# MF-CI_4_1-SDW_-_EXTERNAL.net
KiCad netlist of a schematic drawn in Altium Designer
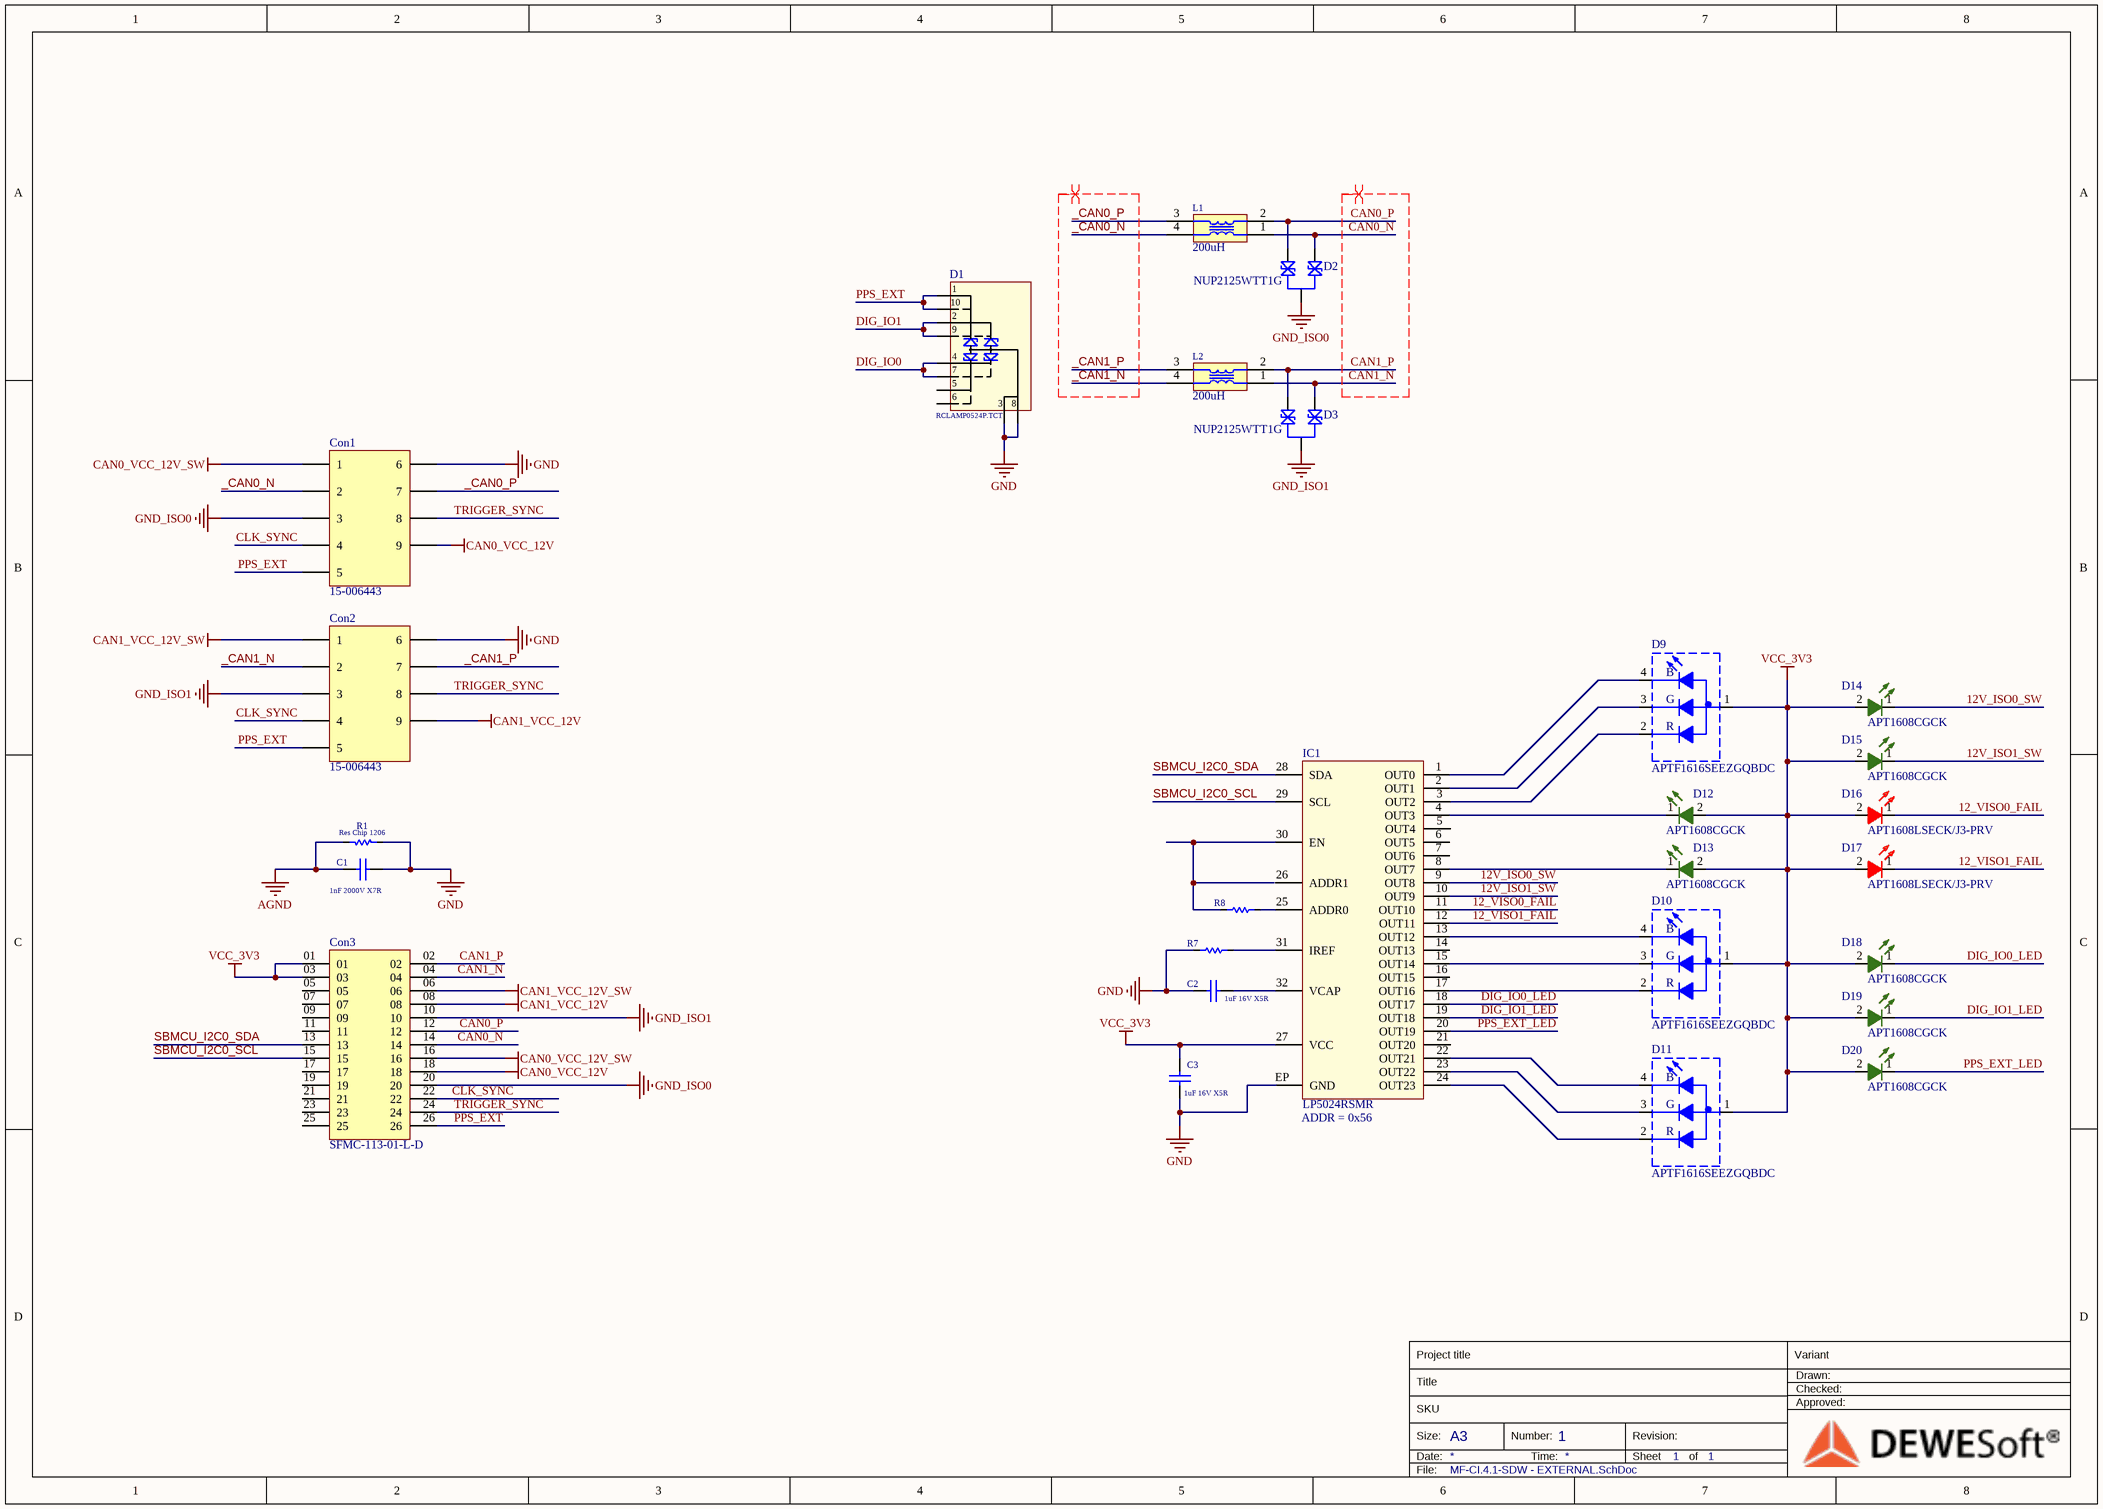
[diagram p0: MF-CI.4.1-SDW - EXTERNAL.SchDoc]

(export (version "E")
  (design (tool "Eeschema 10.0.6"))
  (components
    (comp (ref "C1")
      (value "1nF 2000V X7R")
      (footprint "1206")
      (description "Cap Chip 1nF 2000V X7R 1206")
      (libsource (lib "BBDAQ") (part "Cap"))
    )
    (comp (ref "C2")
      (value "1uF 16V X5R")
      (footprint "0402")
      (description "Capacitor, 1u, 16V, 10%, X5R, 0402")
      (libsource (lib "BBDAQ") (part "CC0402KRX5R7BB105"))
    )
    (comp (ref "C3")
      (value "1uF 16V X5R")
      (footprint "0402")
      (description "Capacitor, 1u, 16V, 10%, X5R, 0402")
      (libsource (lib "BBDAQ") (part "CC0402KRX5R7BB105"))
    )
    (comp (ref "Con1")
      (value "15-006443")
      (footprint "DSUB-9 Male D, 2.74")
      (description "Conn, D-Sub, Male, 9, 2mm, Str, -40/+105")
      (libsource (lib "BBDAQ") (part "15-006443"))
    )
    (comp (ref "Con2")
      (value "15-006443")
      (footprint "DSUB-9 Male D, 2.74")
      (description "Conn, D-Sub, Male, 9, 2mm, Str, -40/+105")
      (libsource (lib "BBDAQ") (part "15-006443"))
    )
    (comp (ref "Con3")
      (value "SFMC-113-01-L-D")
      (footprint "SAMTEC_SFMC-113-01-L-D")
      (description "Conn, Receptacle, Female, 13x2, 1.27mm, Vertical, -55/+125")
      (libsource (lib "BBDAQ") (part "SFMC-113-01-L-D"))
    )
    (comp (ref "D1")
      (value "RCLAMP0524P.TCT")
      (footprint "SLP2510P8")
      (description "Diode array TVS, RCLAMP0524P.TCT")
      (libsource (lib "BBDAQ") (part "CMP-SEM-000069"))
    )
    (comp (ref "D2")
      (value "NUP2125WTT1G")
      (footprint "SOT323-3L(SC-70)")
      (description "Diode dual TVS, SOT323, bidrectional, CAN-FD")
      (libsource (lib "BBDAQ") (part "dual_TVS_diode"))
    )
    (comp (ref "D3")
      (value "NUP2125WTT1G")
      (footprint "SOT323-3L(SC-70)")
      (description "Diode dual TVS, SOT323, bidrectional, CAN-FD")
      (libsource (lib "BBDAQ") (part "dual_TVS_diode"))
    )
    (comp (ref "D9")
      (value "APTF1616SEEZGQBDC")
      (footprint "KINGBRIGHT_APTF1616SEEZGQBDC")
      (description "Diode, LED, Red/Green/Blue, 5V, 20mA, -40/+85")
      (libsource (lib "BBDAQ") (part "APTF1616SEEZGQBDC"))
    )
    (comp (ref "D10")
      (value "APTF1616SEEZGQBDC")
      (footprint "KINGBRIGHT_APTF1616SEEZGQBDC")
      (description "Diode, LED, Red/Green/Blue, 5V, 20mA, -40/+85")
      (libsource (lib "BBDAQ") (part "APTF1616SEEZGQBDC"))
    )
    (comp (ref "D11")
      (value "APTF1616SEEZGQBDC")
      (footprint "KINGBRIGHT_APTF1616SEEZGQBDC")
      (description "Diode, LED, Red/Green/Blue, 5V, 20mA, -40/+85")
      (libsource (lib "BBDAQ") (part "APTF1616SEEZGQBDC"))
    )
    (comp (ref "D12")
      (value "APT1608CGCK")
      (footprint "APT1608CGCK")
      (description "Diode, LED, Green, 5V, 20mA, Vertical, -40/+85, 0603")
      (libsource (lib "BBDAQ") (part "APT1608CGCK"))
    )
    (comp (ref "D13")
      (value "APT1608CGCK")
      (footprint "APT1608CGCK")
      (description "Diode, LED, Green, 5V, 20mA, Vertical, -40/+85, 0603")
      (libsource (lib "BBDAQ") (part "APT1608CGCK"))
    )
    (comp (ref "D14")
      (value "APT1608CGCK")
      (footprint "APT1608CGCK")
      (description "Diode, LED, Green, 5V, 20mA, Vertical, -40/+85, 0603")
      (libsource (lib "BBDAQ") (part "APT1608CGCK"))
    )
    (comp (ref "D15")
      (value "APT1608CGCK")
      (footprint "APT1608CGCK")
      (description "Diode, LED, Green, 5V, 20mA, Vertical, -40/+85, 0603")
      (libsource (lib "BBDAQ") (part "APT1608CGCK"))
    )
    (comp (ref "D16")
      (value "APT1608LSECK/J3-PRV")
      (footprint "Kingbright_APT1608LSECK/J3-PRV")
      (description "Diode, LED, Red, 5V, 20mA, -40/+85")
      (libsource (lib "BBDAQ") (part "APT1608LSECK/J3-PRV"))
    )
    (comp (ref "D17")
      (value "APT1608LSECK/J3-PRV")
      (footprint "Kingbright_APT1608LSECK/J3-PRV")
      (description "Diode, LED, Red, 5V, 20mA, -40/+85")
      (libsource (lib "BBDAQ") (part "APT1608LSECK/J3-PRV"))
    )
    (comp (ref "D18")
      (value "APT1608CGCK")
      (footprint "APT1608CGCK")
      (description "Diode, LED, Green, 5V, 20mA, Vertical, -40/+85, 0603")
      (libsource (lib "BBDAQ") (part "APT1608CGCK"))
    )
    (comp (ref "D19")
      (value "APT1608CGCK")
      (footprint "APT1608CGCK")
      (description "Diode, LED, Green, 5V, 20mA, Vertical, -40/+85, 0603")
      (libsource (lib "BBDAQ") (part "APT1608CGCK"))
    )
    (comp (ref "D20")
      (value "APT1608CGCK")
      (footprint "APT1608CGCK")
      (description "Diode, LED, Green, 5V, 20mA, Vertical, -40/+85, 0603")
      (libsource (lib "BBDAQ") (part "APT1608CGCK"))
    )
    (comp (ref "IC1")
      (value "LP5024RSMR")
      (footprint "QFN-32[8x8]_0,25/0,50_5x5x1_HD[2,10x2,10]")
      (description "IC, LED Driver, 24 LEDs, 2.7-5.5V, 35mA, -40/+85, VFQFN-32")
      (fields (field (name "MANUFACTURER") "TI"))
      (libsource (lib "BBDAQ") (part "LP5024RSMR"))
    )
    (comp (ref "L1")
      (value "200uH")
      (footprint "ACT1210L")
      (description "ACT1210L-201-2P-TL00 -  Filter Common Mode ACT1210L Series 200uH 70mA 2.5mm x 3.9mm x 2.5mm")
      (libsource (lib "BBDAQ") (part "CM_Choke"))
    )
    (comp (ref "L2")
      (value "200uH")
      (footprint "ACT1210L")
      (description "ACT1210L-201-2P-TL00 -  Filter Common Mode ACT1210L Series 200uH 70mA 2.5mm x 3.9mm x 2.5mm")
      (libsource (lib "BBDAQ") (part "CM_Choke"))
    )
    (comp (ref "R1")
      (value "Res Chip 1206")
      (footprint "1206")
      (libsource (lib "BBDAQ") (part "CMP-RST-001901"))
    )
    (comp (ref "R7")
      (value "Res Chip 0402")
      (footprint "0402")
      (libsource (lib "BBDAQ") (part "CMP-RST-001998"))
    )
    (comp (ref "R8")
      (value "Res Chip 0402")
      (footprint "0402")
      (libsource (lib "BBDAQ") (part "CMP-RST-001998"))
    )
  )
  (nets
    (net (code "1") (name "/12V_ISO0_SW") (class "Default")
      (node (ref "D14") (pin "1") (pinfunction "K_1") (pintype "passive"))
      (node (ref "IC1") (pin "9") (pinfunction "OUT8_9") (pintype "passive"))
    )
    (net (code "2") (name "/12V_ISO1_SW") (class "Default")
      (node (ref "D15") (pin "1") (pinfunction "K_1") (pintype "passive"))
      (node (ref "IC1") (pin "10") (pinfunction "OUT9_10") (pintype "passive"))
    )
    (net (code "3") (name "/12_VISO0_FAIL") (class "Default")
      (node (ref "D16") (pin "1") (pinfunction "K_1") (pintype "passive"))
      (node (ref "IC1") (pin "11") (pinfunction "OUT10_11") (pintype "passive"))
    )
    (net (code "4") (name "/12_VISO1_FAIL") (class "Default")
      (node (ref "D17") (pin "1") (pinfunction "K_1") (pintype "passive"))
      (node (ref "IC1") (pin "12") (pinfunction "OUT11_12") (pintype "passive"))
    )
    (net (code "5") (name "/CAN0_N") (class "Default")
      (node (ref "Con3") (pin "14") (pinfunction "14_14") (pintype "passive"))
      (node (ref "D2") (pin "2") (pinfunction "2_2") (pintype "passive"))
      (node (ref "L1") (pin "1") (pintype "passive"))
    )
    (net (code "6") (name "/CAN0_P") (class "Default")
      (node (ref "Con3") (pin "12") (pinfunction "12_12") (pintype "passive"))
      (node (ref "D2") (pin "1") (pinfunction "1_1") (pintype "passive"))
      (node (ref "L1") (pin "2") (pintype "passive"))
    )
    (net (code "7") (name "/CAN1_N") (class "Default")
      (node (ref "Con3") (pin "04") (pinfunction "04_04") (pintype "passive"))
      (node (ref "D3") (pin "2") (pinfunction "2_2") (pintype "passive"))
      (node (ref "L2") (pin "1") (pintype "passive"))
    )
    (net (code "8") (name "/CAN1_P") (class "Default")
      (node (ref "Con3") (pin "02") (pinfunction "02_02") (pintype "passive"))
      (node (ref "D3") (pin "1") (pinfunction "1_1") (pintype "passive"))
      (node (ref "L2") (pin "2") (pintype "passive"))
    )
    (net (code "9") (name "/CLK_SYNC") (class "Default")
      (node (ref "Con1") (pin "4") (pinfunction "4_4") (pintype "passive"))
      (node (ref "Con2") (pin "4") (pinfunction "4_4") (pintype "passive"))
      (node (ref "Con3") (pin "22") (pinfunction "22_22") (pintype "passive"))
    )
    (net (code "10") (name "/DIG_IO0") (class "Default")
      (node (ref "D1") (pin "4") (pinfunction "4_4") (pintype "passive"))
      (node (ref "D1") (pin "7") (pinfunction "7_7") (pintype "passive"))
    )
    (net (code "11") (name "/DIG_IO0_LED") (class "Default")
      (node (ref "D18") (pin "1") (pinfunction "K_1") (pintype "passive"))
      (node (ref "IC1") (pin "18") (pinfunction "OUT17_18") (pintype "passive"))
    )
    (net (code "12") (name "/DIG_IO1") (class "Default")
      (node (ref "D1") (pin "2") (pinfunction "2_2") (pintype "passive"))
      (node (ref "D1") (pin "9") (pinfunction "9_9") (pintype "passive"))
    )
    (net (code "13") (name "/DIG_IO1_LED") (class "Default")
      (node (ref "D19") (pin "1") (pinfunction "K_1") (pintype "passive"))
      (node (ref "IC1") (pin "19") (pinfunction "OUT18_19") (pintype "passive"))
    )
    (net (code "14") (name "/PPS_EXT") (class "Default")
      (node (ref "Con1") (pin "5") (pinfunction "5_5") (pintype "passive"))
      (node (ref "Con2") (pin "5") (pinfunction "5_5") (pintype "passive"))
      (node (ref "Con3") (pin "26") (pinfunction "26_26") (pintype "passive"))
      (node (ref "D1") (pin "1") (pinfunction "1_1") (pintype "passive"))
      (node (ref "D1") (pin "10") (pinfunction "10_10") (pintype "passive"))
    )
    (net (code "15") (name "/PPS_EXT_LED") (class "Default")
      (node (ref "D20") (pin "1") (pinfunction "K_1") (pintype "passive"))
      (node (ref "IC1") (pin "20") (pinfunction "OUT19_20") (pintype "passive"))
    )
    (net (code "16") (name "/SBMCU_I2C0_SCL") (class "Default")
      (node (ref "Con3") (pin "15") (pinfunction "15_15") (pintype "passive"))
      (node (ref "IC1") (pin "29") (pinfunction "SCL_29") (pintype "passive"))
    )
    (net (code "17") (name "/SBMCU_I2C0_SDA") (class "Default")
      (node (ref "Con3") (pin "13") (pinfunction "13_13") (pintype "passive"))
      (node (ref "IC1") (pin "28") (pinfunction "SDA_28") (pintype "passive"))
    )
    (net (code "18") (name "/TRIGGER_SYNC") (class "Default")
      (node (ref "Con1") (pin "8") (pinfunction "8_8") (pintype "passive"))
      (node (ref "Con2") (pin "8") (pinfunction "8_8") (pintype "passive"))
      (node (ref "Con3") (pin "24") (pinfunction "24_24") (pintype "passive"))
    )
    (net (code "19") (name "/_CAN0_N") (class "Default")
      (node (ref "Con1") (pin "2") (pinfunction "2_2") (pintype "passive"))
      (node (ref "L1") (pin "4") (pintype "passive"))
    )
    (net (code "20") (name "/_CAN0_P") (class "Default")
      (node (ref "Con1") (pin "7") (pinfunction "7_7") (pintype "passive"))
      (node (ref "L1") (pin "3") (pintype "passive"))
    )
    (net (code "21") (name "/_CAN1_N") (class "Default")
      (node (ref "Con2") (pin "2") (pinfunction "2_2") (pintype "passive"))
      (node (ref "L2") (pin "4") (pintype "passive"))
    )
    (net (code "22") (name "/_CAN1_P") (class "Default")
      (node (ref "Con2") (pin "7") (pinfunction "7_7") (pintype "passive"))
      (node (ref "L2") (pin "3") (pintype "passive"))
    )
    (net (code "23") (name "AGND") (class "Default")
      (node (ref "C1") (pin "1") (pinfunction "1_1") (pintype "passive"))
      (node (ref "R1") (pin "2") (pinfunction "2_2") (pintype "passive"))
    )
    (net (code "24") (name "CAN0_VCC_12V") (class "Default")
      (node (ref "Con1") (pin "9") (pinfunction "9_9") (pintype "passive"))
      (node (ref "Con3") (pin "18") (pinfunction "18_18") (pintype "passive"))
    )
    (net (code "25") (name "CAN0_VCC_12V_SW") (class "Default")
      (node (ref "Con1") (pin "1") (pinfunction "1_1") (pintype "passive"))
      (node (ref "Con3") (pin "16") (pinfunction "16_16") (pintype "passive"))
    )
    (net (code "26") (name "CAN1_VCC_12V") (class "Default")
      (node (ref "Con2") (pin "9") (pinfunction "9_9") (pintype "passive"))
      (node (ref "Con3") (pin "08") (pinfunction "08_08") (pintype "passive"))
    )
    (net (code "27") (name "CAN1_VCC_12V_SW") (class "Default")
      (node (ref "Con2") (pin "1") (pinfunction "1_1") (pintype "passive"))
      (node (ref "Con3") (pin "06") (pinfunction "06_06") (pintype "passive"))
    )
    (net (code "28") (name "GND") (class "Default")
      (node (ref "C1") (pin "2") (pinfunction "2_2") (pintype "passive"))
      (node (ref "C2") (pin "2") (pinfunction "2_2") (pintype "passive"))
      (node (ref "C3") (pin "1") (pinfunction "1_1") (pintype "passive"))
      (node (ref "Con1") (pin "6") (pinfunction "6_6") (pintype "passive"))
      (node (ref "Con2") (pin "6") (pinfunction "6_6") (pintype "passive"))
      (node (ref "D1") (pin "3") (pinfunction "3_3") (pintype "passive"))
      (node (ref "D1") (pin "8") (pinfunction "8_8") (pintype "passive"))
      (node (ref "IC1") (pin "EP") (pinfunction "GND_EP") (pintype "passive"))
      (node (ref "R1") (pin "1") (pinfunction "1_1") (pintype "passive"))
      (node (ref "R7") (pin "2") (pinfunction "2_2") (pintype "passive"))
    )
    (net (code "29") (name "GND_ISO0") (class "Default")
      (node (ref "Con1") (pin "3") (pinfunction "3_3") (pintype "passive"))
      (node (ref "Con3") (pin "20") (pinfunction "20_20") (pintype "passive"))
      (node (ref "D2") (pin "3") (pinfunction "3_3") (pintype "passive"))
    )
    (net (code "30") (name "GND_ISO1") (class "Default")
      (node (ref "Con2") (pin "3") (pinfunction "3_3") (pintype "passive"))
      (node (ref "Con3") (pin "10") (pinfunction "10_10") (pintype "passive"))
      (node (ref "D3") (pin "3") (pinfunction "3_3") (pintype "passive"))
    )
    (net (code "31") (name "Net-(D12-K)") (class "Default")
      (node (ref "D12") (pin "1") (pinfunction "K_1") (pintype "passive"))
      (node (ref "IC1") (pin "4") (pinfunction "OUT3_4") (pintype "passive"))
    )
    (net (code "32") (name "Net-(D13-K)") (class "Default")
      (node (ref "D13") (pin "1") (pinfunction "K_1") (pintype "passive"))
      (node (ref "IC1") (pin "8") (pinfunction "OUT7_8") (pintype "passive"))
    )
    (net (code "33") (name "Net-(IC1-ADDR0)") (class "Default")
      (node (ref "IC1") (pin "25") (pinfunction "ADDR0_25") (pintype "passive"))
      (node (ref "R8") (pin "2") (pinfunction "2_2") (pintype "passive"))
    )
    (net (code "34") (name "Net-(IC1-EN)") (class "Default")
      (node (ref "IC1") (pin "30") (pinfunction "EN_30") (pintype "passive"))
      (node (ref "R8") (pin "1") (pinfunction "1_1") (pintype "passive"))
    )
    (net (code "35") (name "Net-(IC1-IREF)") (class "Default")
      (node (ref "IC1") (pin "31") (pinfunction "IREF_31") (pintype "passive"))
      (node (ref "R7") (pin "1") (pinfunction "1_1") (pintype "passive"))
    )
    (net (code "36") (name "Net-(IC1-OUT0)") (class "Default")
      (node (ref "D9") (pin "4") (pinfunction "K_4") (pintype "passive"))
      (node (ref "IC1") (pin "1") (pinfunction "OUT0_1") (pintype "passive"))
    )
    (net (code "37") (name "Net-(IC1-OUT1)") (class "Default")
      (node (ref "D9") (pin "3") (pinfunction "K_3") (pintype "passive"))
      (node (ref "IC1") (pin "2") (pinfunction "OUT1_2") (pintype "passive"))
    )
    (net (code "38") (name "Net-(IC1-OUT2)") (class "Default")
      (node (ref "D9") (pin "2") (pinfunction "K_2") (pintype "passive"))
      (node (ref "IC1") (pin "3") (pinfunction "OUT2_3") (pintype "passive"))
    )
    (net (code "39") (name "Net-(IC1-OUT12)") (class "Default")
      (node (ref "D10") (pin "4") (pinfunction "K_4") (pintype "passive"))
      (node (ref "IC1") (pin "13") (pinfunction "OUT12_13") (pintype "passive"))
    )
    (net (code "40") (name "Net-(IC1-OUT14)") (class "Default")
      (node (ref "D10") (pin "3") (pinfunction "K_3") (pintype "passive"))
      (node (ref "IC1") (pin "15") (pinfunction "OUT14_15") (pintype "passive"))
    )
    (net (code "41") (name "Net-(IC1-OUT16)") (class "Default")
      (node (ref "D10") (pin "2") (pinfunction "K_2") (pintype "passive"))
      (node (ref "IC1") (pin "17") (pinfunction "OUT16_17") (pintype "passive"))
    )
    (net (code "42") (name "Net-(IC1-OUT21)") (class "Default")
      (node (ref "D11") (pin "4") (pinfunction "K_4") (pintype "passive"))
      (node (ref "IC1") (pin "22") (pinfunction "OUT21_22") (pintype "passive"))
    )
    (net (code "43") (name "Net-(IC1-OUT22)") (class "Default")
      (node (ref "D11") (pin "3") (pinfunction "K_3") (pintype "passive"))
      (node (ref "IC1") (pin "23") (pinfunction "OUT22_23") (pintype "passive"))
    )
    (net (code "44") (name "Net-(IC1-OUT23)") (class "Default")
      (node (ref "D11") (pin "2") (pinfunction "K_2") (pintype "passive"))
      (node (ref "IC1") (pin "24") (pinfunction "OUT23_24") (pintype "passive"))
    )
    (net (code "45") (name "Net-(IC1-VCAP)") (class "Default")
      (node (ref "C2") (pin "1") (pinfunction "1_1") (pintype "passive"))
      (node (ref "IC1") (pin "32") (pinfunction "VCAP_32") (pintype "passive"))
    )
    (net (code "46") (name "VCC_3V3") (class "Default")
      (node (ref "C3") (pin "2") (pinfunction "2_2") (pintype "passive"))
      (node (ref "Con3") (pin "01") (pinfunction "01_01") (pintype "passive"))
      (node (ref "Con3") (pin "03") (pinfunction "03_03") (pintype "passive"))
      (node (ref "D10") (pin "1") (pinfunction "A_1") (pintype "passive"))
      (node (ref "D11") (pin "1") (pinfunction "A_1") (pintype "passive"))
      (node (ref "D12") (pin "2") (pinfunction "A_2") (pintype "passive"))
      (node (ref "D13") (pin "2") (pinfunction "A_2") (pintype "passive"))
      (node (ref "D14") (pin "2") (pinfunction "A_2") (pintype "passive"))
      (node (ref "D15") (pin "2") (pinfunction "A_2") (pintype "passive"))
      (node (ref "D16") (pin "2") (pinfunction "A_2") (pintype "passive"))
      (node (ref "D17") (pin "2") (pinfunction "A_2") (pintype "passive"))
      (node (ref "D18") (pin "2") (pinfunction "A_2") (pintype "passive"))
      (node (ref "D19") (pin "2") (pinfunction "A_2") (pintype "passive"))
      (node (ref "D20") (pin "2") (pinfunction "A_2") (pintype "passive"))
      (node (ref "D9") (pin "1") (pinfunction "A_1") (pintype "passive"))
      (node (ref "IC1") (pin "27") (pinfunction "VCC_27") (pintype "passive"))
    )
    (net (code "47") (name "unconnected-(Con3-Pad05)") (class "Default")
      (node (ref "Con3") (pin "05") (pinfunction "05_05") (pintype "passive"))
    )
    (net (code "48") (name "unconnected-(Con3-Pad07)") (class "Default")
      (node (ref "Con3") (pin "07") (pinfunction "07_07") (pintype "passive"))
    )
    (net (code "49") (name "unconnected-(Con3-Pad09)") (class "Default")
      (node (ref "Con3") (pin "09") (pinfunction "09_09") (pintype "passive"))
    )
    (net (code "50") (name "unconnected-(Con3-Pad11)") (class "Default")
      (node (ref "Con3") (pin "11") (pinfunction "11_11") (pintype "passive"))
    )
    (net (code "51") (name "unconnected-(Con3-Pad17)") (class "Default")
      (node (ref "Con3") (pin "17") (pinfunction "17_17") (pintype "passive"))
    )
    (net (code "52") (name "unconnected-(Con3-Pad19)") (class "Default")
      (node (ref "Con3") (pin "19") (pinfunction "19_19") (pintype "passive"))
    )
    (net (code "53") (name "unconnected-(Con3-Pad21)") (class "Default")
      (node (ref "Con3") (pin "21") (pinfunction "21_21") (pintype "passive"))
    )
    (net (code "54") (name "unconnected-(Con3-Pad23)") (class "Default")
      (node (ref "Con3") (pin "23") (pinfunction "23_23") (pintype "passive"))
    )
    (net (code "55") (name "unconnected-(Con3-Pad25)") (class "Default")
      (node (ref "Con3") (pin "25") (pinfunction "25_25") (pintype "passive"))
    )
    (net (code "56") (name "unconnected-(D1-Pad5)") (class "Default")
      (node (ref "D1") (pin "5") (pinfunction "5_5") (pintype "passive"))
    )
    (net (code "57") (name "unconnected-(D1-Pad6)") (class "Default")
      (node (ref "D1") (pin "6") (pinfunction "6_6") (pintype "passive"))
    )
    (net (code "58") (name "unconnected-(IC1-ADDR1-Pad26)") (class "Default")
      (node (ref "IC1") (pin "26") (pinfunction "ADDR1_26") (pintype "passive"))
    )
    (net (code "59") (name "unconnected-(IC1-OUT4-Pad5)") (class "Default")
      (node (ref "IC1") (pin "5") (pinfunction "OUT4_5") (pintype "passive"))
    )
    (net (code "60") (name "unconnected-(IC1-OUT5-Pad6)") (class "Default")
      (node (ref "IC1") (pin "6") (pinfunction "OUT5_6") (pintype "passive"))
    )
    (net (code "61") (name "unconnected-(IC1-OUT6-Pad7)") (class "Default")
      (node (ref "IC1") (pin "7") (pinfunction "OUT6_7") (pintype "passive"))
    )
    (net (code "62") (name "unconnected-(IC1-OUT13-Pad14)") (class "Default")
      (node (ref "IC1") (pin "14") (pinfunction "OUT13_14") (pintype "passive"))
    )
    (net (code "63") (name "unconnected-(IC1-OUT15-Pad16)") (class "Default")
      (node (ref "IC1") (pin "16") (pinfunction "OUT15_16") (pintype "passive"))
    )
    (net (code "64") (name "unconnected-(IC1-OUT20-Pad21)") (class "Default")
      (node (ref "IC1") (pin "21") (pinfunction "OUT20_21") (pintype "passive"))
    )
  )
)
